# PG13__USB_Ports.net
KiCad netlist of a schematic drawn in Altium Designer
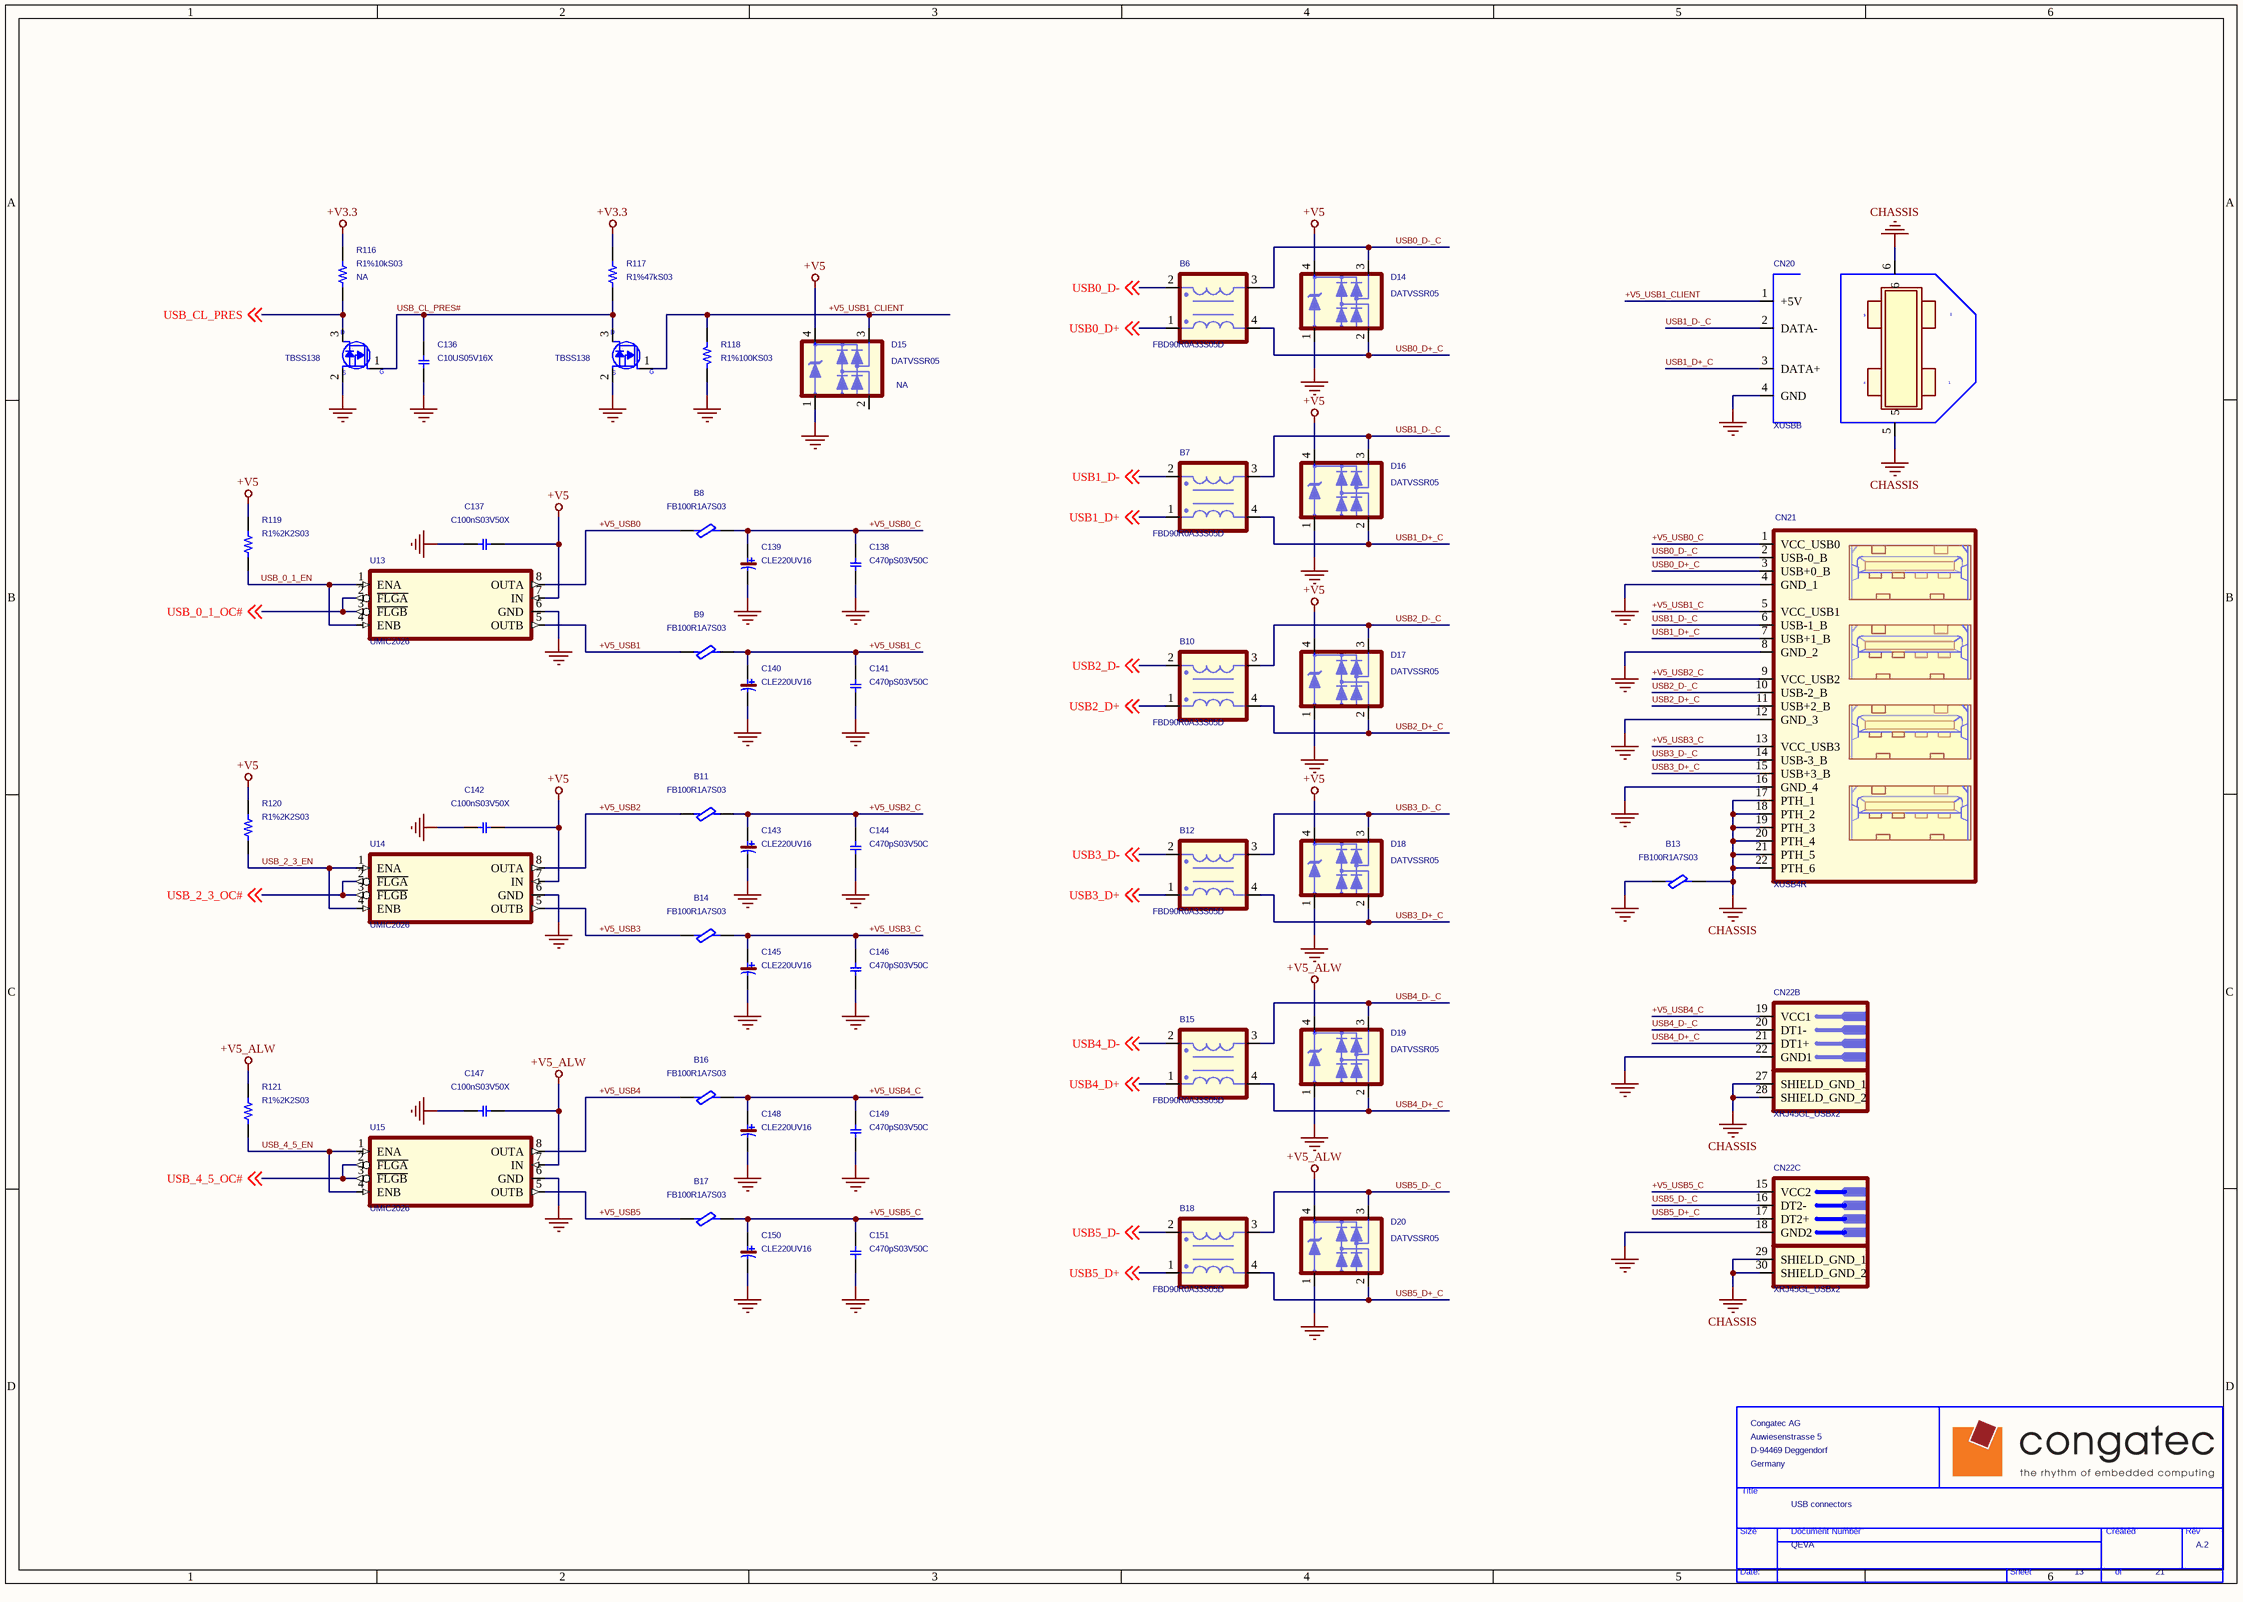
[diagram p0: PG13_ USB Ports.SchDoc]

(export (version "E")
  (design (tool "Eeschema 10.0.6"))
  (components
    (comp (ref "B6")
      (value "FBD90R0A33S05D")
      (description "* Inductor Common-MODE FILTER ACM2012-900-2P SMD")
      (fields (field (name "PART_NUMBER") "43500027") (field (name "PART NUMBER") "1212309007"))
      (libsource (lib "*") (part "1212_FILTER_0"))
    )
    (comp (ref "B7")
      (value "FBD90R0A33S05D")
      (description "* Inductor Common-MODE FILTER ACM2012-900-2P SMD")
      (fields (field (name "PART_NUMBER") "43500027") (field (name "PART NUMBER") "1212309007"))
      (libsource (lib "*") (part "1212_FILTER_0"))
    )
    (comp (ref "B8")
      (value "FB100R1A7S03")
      (description "Bead 120 +-25% 2A SMD 0603 BLM18PG121SN1 WO/Pb")
      (fields (field (name "PART_NUMBER") "43500008") (field (name "PART NUMBER") "1212000056"))
      (libsource (lib "*") (part "1212_BEAD_0"))
    )
    (comp (ref "B9")
      (value "FB100R1A7S03")
      (description "Bead 120 +-25% 2A SMD 0603 BLM18PG121SN1 WO/Pb")
      (fields (field (name "PART_NUMBER") "43500008") (field (name "PART NUMBER") "1212000056"))
      (libsource (lib "*") (part "1212_BEAD_0"))
    )
    (comp (ref "B10")
      (value "FBD90R0A33S05D")
      (description "* Inductor Common-MODE FILTER ACM2012-900-2P SMD")
      (fields (field (name "PART_NUMBER") "43500027") (field (name "PART NUMBER") "1212309007"))
      (libsource (lib "*") (part "1212_FILTER_0"))
    )
    (comp (ref "B11")
      (value "FB100R1A7S03")
      (description "Bead 120 +-25% 2A SMD 0603 BLM18PG121SN1 WO/Pb")
      (fields (field (name "PART_NUMBER") "43500008") (field (name "PART NUMBER") "1212000056"))
      (libsource (lib "*") (part "1212_BEAD_0"))
    )
    (comp (ref "B12")
      (value "FBD90R0A33S05D")
      (description "* Inductor Common-MODE FILTER ACM2012-900-2P SMD")
      (fields (field (name "PART_NUMBER") "43500027") (field (name "PART NUMBER") "1212309007"))
      (libsource (lib "*") (part "1212_FILTER_0"))
    )
    (comp (ref "B13")
      (value "FB100R1A7S03")
      (description "Bead 120 +-25% 2A SMD 0603 BLM18PG121SN1 WO/Pb")
      (fields
        (field (name "PART_NUMBER") "43500008")
        (field (name "MANUFACTURE PART NUMBER") "BLM18PG121SN1")
      )
      (libsource (lib "*") (part "1212_BEAD_0"))
    )
    (comp (ref "B14")
      (value "FB100R1A7S03")
      (description "Bead 120 +-25% 2A SMD 0603 BLM18PG121SN1 WO/Pb")
      (fields (field (name "PART_NUMBER") "43500008") (field (name "PART NUMBER") "1212000056"))
      (libsource (lib "*") (part "1212_BEAD_0"))
    )
    (comp (ref "B15")
      (value "FBD90R0A33S05D")
      (description "* Inductor Common-MODE FILTER ACM2012-900-2P SMD")
      (fields (field (name "PART_NUMBER") "43500027") (field (name "PART NUMBER") "1212309007"))
      (libsource (lib "*") (part "1212_FILTER_0"))
    )
    (comp (ref "B16")
      (value "FB100R1A7S03")
      (description "Bead 120 +-25% 2A SMD 0603 BLM18PG121SN1 WO/Pb")
      (fields (field (name "PART_NUMBER") "43500008") (field (name "PART NUMBER") "1212000056"))
      (libsource (lib "*") (part "1212_BEAD_0"))
    )
    (comp (ref "B17")
      (value "FB100R1A7S03")
      (description "Bead 120 +-25% 2A SMD 0603 BLM18PG121SN1 WO/Pb")
      (fields (field (name "PART_NUMBER") "43500008") (field (name "PART NUMBER") "1212000056"))
      (libsource (lib "*") (part "1212_BEAD_0"))
    )
    (comp (ref "B18")
      (value "FBD90R0A33S05D")
      (description "* Inductor Common-MODE FILTER ACM2012-900-2P SMD")
      (fields (field (name "PART_NUMBER") "43500027") (field (name "PART NUMBER") "1212309007"))
      (libsource (lib "*") (part "1212_FILTER_0"))
    )
    (comp (ref "C136")
      (value "C10US05V16X")
      (description "CAP 10u 6.3V +/-10% SMD 0805 MLCC X5R KEMET")
      (fields (field (name "PART NUMBER") "1100000316") (field (name "TOLERANCE") "10%"))
      (libsource (lib "*") (part "11_C_0"))
    )
    (comp (ref "C137")
      (value "C100nS03V50X")
      (description "CAP 0.1U 50V +-10% SMD 0603 X7R WO/Pb")
      (fields
        (field (name "PART_NUMBER") "41000289")
        (field (name "MANUFACTURE PART NUMBER") "C1608X7R1H104KT223858615649")
      )
      (libsource (lib "*") (part "11_C_0"))
    )
    (comp (ref "C138")
      (value "C470pS03V50C")
      (description "CAP 470pF 50V 10% 0603 SMD  MCC")
      (fields (field (name "PART_NUMBER") "41000322") (field (name "PART NUMBER") "1124547180"))
      (libsource (lib "*") (part "11_C_0"))
    )
    (comp (ref "C139")
      (value "CLE220UV16")
      (description "*CAP 220uF 16V +-20% SMD 6.3?*7.7 EC LOW ESR")
      (fields (field (name "PART_NUMBER") "41000366") (field (name "PART NUMBER") "1111622190"))
      (libsource (lib "*") (part "11_C_POLAR_0"))
    )
    (comp (ref "C140")
      (value "CLE220UV16")
      (description "*CAP 220uF 16V +-20% SMD 6.3?*7.7 EC LOW ESR")
      (fields (field (name "PART_NUMBER") "41000366") (field (name "PART NUMBER") "1111622190"))
      (libsource (lib "*") (part "11_C_POLAR_0"))
    )
    (comp (ref "C141")
      (value "C470pS03V50C")
      (description "CAP 470pF 50V 10% 0603 SMD  MCC")
      (fields (field (name "PART_NUMBER") "41000322") (field (name "PART NUMBER") "1124547180"))
      (libsource (lib "*") (part "11_C_0"))
    )
    (comp (ref "C142")
      (value "C100nS03V50X")
      (description "CAP 0.1U 50V +-10% SMD 0603 X7R WO/Pb")
      (fields (field (name "PART NUMBER") "1100000214") (field (name "TOLERANCE") "10%"))
      (libsource (lib "*") (part "11_C_0"))
    )
    (comp (ref "C143")
      (value "CLE220UV16")
      (description "*CAP 220uF 16V +-20% SMD 6.3?*7.7 EC LOW ESR")
      (fields (field (name "PART_NUMBER") "41000366") (field (name "PART NUMBER") "1111622190"))
      (libsource (lib "*") (part "11_C_POLAR_0"))
    )
    (comp (ref "C144")
      (value "C470pS03V50C")
      (description "CAP 470pF 50V 10% 0603 SMD  MCC")
      (fields (field (name "PART_NUMBER") "41000322") (field (name "PART NUMBER") "1124547180"))
      (libsource (lib "*") (part "11_C_0"))
    )
    (comp (ref "C145")
      (value "CLE220UV16")
      (description "*CAP 220uF 16V +-20% SMD 6.3?*7.7 EC LOW ESR")
      (fields (field (name "PART_NUMBER") "41000366") (field (name "PART NUMBER") "1111622190"))
      (libsource (lib "*") (part "11_C_POLAR_0"))
    )
    (comp (ref "C146")
      (value "C470pS03V50C")
      (description "CAP 470pF 50V 10% 0603 SMD  MCC")
      (fields (field (name "PART_NUMBER") "41000322") (field (name "PART NUMBER") "1124547180"))
      (libsource (lib "*") (part "11_C_0"))
    )
    (comp (ref "C147")
      (value "C100nS03V50X")
      (description "CAP 0.1U 50V +-10% SMD 0603 X7R WO/Pb")
      (fields (field (name "PART NUMBER") "1100000214") (field (name "TOLERANCE") "10%"))
      (libsource (lib "*") (part "11_C_0"))
    )
    (comp (ref "C148")
      (value "CLE220UV16")
      (description "*CAP 220uF 16V +-20% SMD 6.3?*7.7 EC LOW ESR")
      (fields (field (name "PART_NUMBER") "41000366") (field (name "PART NUMBER") "1111622190"))
      (libsource (lib "*") (part "11_C_POLAR_0"))
    )
    (comp (ref "C149")
      (value "C470pS03V50C")
      (description "CAP 470pF 50V 10% 0603 SMD  MCC")
      (fields (field (name "PART_NUMBER") "41000322") (field (name "PART NUMBER") "1124547180"))
      (libsource (lib "*") (part "11_C_0"))
    )
    (comp (ref "C150")
      (value "CLE220UV16")
      (description "*CAP 220uF 16V +-20% SMD 6.3?*7.7 EC LOW ESR")
      (fields (field (name "PART_NUMBER") "41000366") (field (name "PART NUMBER") "1111622190"))
      (libsource (lib "*") (part "11_C_POLAR_0"))
    )
    (comp (ref "C151")
      (value "C470pS03V50C")
      (description "CAP 470pF 50V 10% 0603 SMD  MCC")
      (fields (field (name "PART_NUMBER") "41000322") (field (name "PART NUMBER") "1124547180"))
      (libsource (lib "*") (part "11_C_0"))
    )
    (comp (ref "CN20")
      (value "XUSBB")
      (description "USB CONN. 4P 90D(M) TYPE B SUYIN")
      (fields
        (field (name "PART_NUMBER") "41500326")
        (field (name "MANUFACTURE PART NUMBER") "020123MR004S200PA")
      )
      (libsource (lib "*") (part "1654_USB-BT-V_0"))
    )
    (comp (ref "CN21")
      (value "XUSB4R")
      (description "USB CONN. 16P 90D(M) DIP 4PORT TYPE A")
      (fields
        (field (name "PART NUMBER") "1654000162")
        (field (name "MANUFACTURE PART NUMBER") "0-1734383-1")
      )
      (libsource (lib "*") (part "1654_USBX4-V_ATYPE_0"))
    )
    (comp (ref "CN22")
      (value "XRJ45GL_USBx2")
      (description "PhoneJack RJ45+USB*2 90D(F) W/LED&XFMR DIP")
      (fields (field (name "PART NUMBER") "165250820M") (field (name "PART_NUMBER") "41500328"))
      (libsource (lib "*") (part "1652_RJ45-P3515619W9_0"))
    )
    (comp (ref "D14")
      (value "DATVSSR05")
      (description "Diode TVS SR05.TCT SMD SOT-143 4P 15KV SEMTECH")
      (fields (field (name "PART_NUMBER") "42500011") (field (name "MANUFACTURE PART NUMBER") "SR05.TCT"))
      (libsource (lib "*") (part "130_TVS_SOT-143-SR05_0"))
    )
    (comp (ref "D15")
      (value "DATVSSR05")
      (description "Diode TVS SR05.TCT SMD SOT-143 4P 15KV SEMTECH")
      (fields
        (field (name "MANUFACTURE PART NUMBER") "SR05.TCT")
        (field (name "PART NUMBER") "1300000127")
        (field (name "MOUNTED") "NA")
      )
      (libsource (lib "*") (part "130_TVS_SOT-143-SR05_0"))
    )
    (comp (ref "D16")
      (value "DATVSSR05")
      (description "Diode TVS SR05.TCT SMD SOT-143 4P 15KV SEMTECH")
      (fields (field (name "PART_NUMBER") "42500011") (field (name "MANUFACTURE PART NUMBER") "SR05.TCT"))
      (libsource (lib "*") (part "130_TVS_SOT-143-SR05_0"))
    )
    (comp (ref "D17")
      (value "DATVSSR05")
      (description "Diode TVS SR05.TCT SMD SOT-143 4P 15KV SEMTECH")
      (fields (field (name "PART_NUMBER") "42500011") (field (name "MANUFACTURE PART NUMBER") "SR05.TCT"))
      (libsource (lib "*") (part "130_TVS_SOT-143-SR05_0"))
    )
    (comp (ref "D18")
      (value "DATVSSR05")
      (description "Diode TVS SR05.TCT SMD SOT-143 4P 15KV SEMTECH")
      (fields (field (name "PART_NUMBER") "42500011") (field (name "MANUFACTURE PART NUMBER") "SR05.TCT"))
      (libsource (lib "*") (part "130_TVS_SOT-143-SR05_0"))
    )
    (comp (ref "D19")
      (value "DATVSSR05")
      (description "Diode TVS SR05.TCT SMD SOT-143 4P 15KV SEMTECH")
      (fields (field (name "PART_NUMBER") "42500011") (field (name "PART NUMBER") "1300000127"))
      (libsource (lib "*") (part "130_TVS_SOT-143-SR05_0"))
    )
    (comp (ref "D20")
      (value "DATVSSR05")
      (description "Diode TVS SR05.TCT SMD SOT-143 4P 15KV SEMTECH")
      (fields (field (name "PART_NUMBER") "42500011") (field (name "PART NUMBER") "1300000127"))
      (libsource (lib "*") (part "130_TVS_SOT-143-SR05_0"))
    )
    (comp (ref "Q11")
      (value "TBSS138")
      (description "MOSFET MPN BSS138_NL SMD SOT-23 3P 50V N-channe")
      (fields (field (name "PART_NUMBER") "44000026") (field (name "MANUFACTURE PART NUMBER") "BSS138_NL"))
      (libsource (lib "*") (part "131_SOT-23A_GSD_0"))
    )
    (comp (ref "Q12")
      (value "TBSS138")
      (description "MOSFET MPN BSS138_NL SMD SOT-23 3P 50V N-channe")
      (fields (field (name "PART_NUMBER") "44000026") (field (name "PART NUMBER") "1310000011"))
      (libsource (lib "*") (part "131_SOT-23A_GSD_0"))
    )
    (comp (ref "R116")
      (value "R1%10kS03")
      (description "R 10K 1/10W 1% SMD 0603 CR WO/Pb")
      (fields
        (field (name "MOUNTED") "NA")
        (field (name "MANUFACTURE PART NUMBER") "RCT02***FTP0603WAF1002T5E2322 704 61003LRC0603FR-0710KLRM06FTN1002WR06X8200JT")
        (field (name "TOLERANCE") "1%")
      )
      (libsource (lib "*") (part "10_R_0_Dup1"))
    )
    (comp (ref "R117")
      (value "R1%47kS03")
      (description "47K 1/10W 5% 0603 CR WO/Pb")
      (fields
        (field (name "MANUFACTURE PART NUMBER") "0603WAJ0473T5E232270260473LRM06JTN473")
        (field (name "TOLERANCE") "5%")
      )
      (libsource (lib "*") (part "10_R_0_Dup1"))
    )
    (comp (ref "R118")
      (value "R1%100KS03")
      (description "R 100K 1/10W 1% SMD 0603 CR")
      (fields (field (name "PART_NUMBER") "45501496") (field (name "PART NUMBER") "105A510033"))
      (libsource (lib "*") (part "10_R_0_Dup1"))
    )
    (comp (ref "R119")
      (value "R1%2K2S03")
      (description "R 2.2K 1/10W 1% SMD 0603 CR")
      (fields (field (name "PART_NUMBER") "45502036") (field (name "PART NUMBER") "105A522013"))
      (libsource (lib "*") (part "10_R_0_Dup1"))
    )
    (comp (ref "R120")
      (value "R1%2K2S03")
      (description "R 2.2K 1/10W 1% SMD 0603 CR")
      (fields (field (name "PART_NUMBER") "45502036") (field (name "PART NUMBER") "105A522013"))
      (libsource (lib "*") (part "10_R_0_Dup1"))
    )
    (comp (ref "R121")
      (value "R1%2K2S03")
      (description "R 2.2K 1/10W 1% SMD 0603 CR")
      (fields (field (name "PART_NUMBER") "45502036") (field (name "PART NUMBER") "105A522013"))
      (libsource (lib "*") (part "10_R_0_Dup1"))
    )
    (comp (ref "U13")
      (value "UMIC2026")
      (description "IC SMD MIC2026-1YM SOIC8 WO/Pb MICREL")
      (fields (field (name "PART_NUMBER") "43000105") (field (name "MANUFACTURE PART NUMBER") "MIC2026-1YM"))
      (libsource (lib "*") (part "14S_MICREL_MIC2026-1YM_0"))
    )
    (comp (ref "U14")
      (value "UMIC2026")
      (description "IC SMD MIC2026-1YM SOIC8 WO/Pb MICREL")
      (fields (field (name "PART_NUMBER") "43000105") (field (name "PART NUMBER") "14S2202600"))
      (libsource (lib "*") (part "14S_MICREL_MIC2026-1YM_0"))
    )
    (comp (ref "U15")
      (value "UMIC2026")
      (description "IC SMD MIC2026-1YM SOIC8 WO/Pb MICREL")
      (fields (field (name "PART_NUMBER") "43000105") (field (name "PART NUMBER") "14S2202600"))
      (libsource (lib "*") (part "14S_MICREL_MIC2026-1YM_0"))
    )
  )
  (nets
    (net (code "1") (name "+V3.3") (class "Default")
      (node (ref "R116") (pin "1") (pinfunction "1_1") (pintype "passive"))
      (node (ref "R117") (pin "1") (pinfunction "1_1") (pintype "passive"))
    )
    (net (code "2") (name "+V5") (class "Default")
      (node (ref "C137") (pin "2") (pinfunction "2_2") (pintype "passive"))
      (node (ref "C142") (pin "2") (pinfunction "2_2") (pintype "passive"))
      (node (ref "D14") (pin "4") (pinfunction "CATHODE_4") (pintype "passive"))
      (node (ref "D15") (pin "4") (pinfunction "CATHODE_4") (pintype "passive"))
      (node (ref "D16") (pin "4") (pinfunction "CATHODE_4") (pintype "passive"))
      (node (ref "D17") (pin "4") (pinfunction "CATHODE_4") (pintype "passive"))
      (node (ref "D18") (pin "4") (pinfunction "CATHODE_4") (pintype "passive"))
      (node (ref "R119") (pin "2") (pinfunction "2_2") (pintype "passive"))
      (node (ref "R120") (pin "2") (pinfunction "2_2") (pintype "passive"))
      (node (ref "U13") (pin "7") (pinfunction "IN_7") (pintype "input"))
      (node (ref "U14") (pin "7") (pinfunction "IN_7") (pintype "input"))
    )
    (net (code "3") (name "+V5_ALW") (class "Default")
      (node (ref "C147") (pin "2") (pinfunction "2_2") (pintype "passive"))
      (node (ref "D19") (pin "4") (pinfunction "CATHODE_4") (pintype "passive"))
      (node (ref "D20") (pin "4") (pinfunction "CATHODE_4") (pintype "passive"))
      (node (ref "R121") (pin "2") (pinfunction "2_2") (pintype "passive"))
      (node (ref "U15") (pin "7") (pinfunction "IN_7") (pintype "input"))
    )
    (net (code "4") (name "/+V5_USB0") (class "Default")
      (node (ref "B8") (pin "1") (pinfunction "1_1") (pintype "passive"))
      (node (ref "U13") (pin "8") (pinfunction "OUTA_8") (pintype "output"))
    )
    (net (code "5") (name "/+V5_USB0_C") (class "Default")
      (node (ref "B8") (pin "2") (pinfunction "2_2") (pintype "passive"))
      (node (ref "C138") (pin "1") (pinfunction "1_1") (pintype "passive"))
      (node (ref "C139") (pin "1") (pinfunction "1_1") (pintype "passive"))
      (node (ref "CN21") (pin "1") (pinfunction "VCC_USB0_1") (pintype "passive"))
    )
    (net (code "6") (name "/+V5_USB1") (class "Default")
      (node (ref "B9") (pin "1") (pinfunction "1_1") (pintype "passive"))
      (node (ref "U13") (pin "5") (pinfunction "OUTB_5") (pintype "output"))
    )
    (net (code "7") (name "/+V5_USB1_C") (class "Default")
      (node (ref "B9") (pin "2") (pinfunction "2_2") (pintype "passive"))
      (node (ref "C140") (pin "1") (pinfunction "1_1") (pintype "passive"))
      (node (ref "C141") (pin "1") (pinfunction "1_1") (pintype "passive"))
      (node (ref "CN21") (pin "5") (pinfunction "VCC_USB1_5") (pintype "passive"))
    )
    (net (code "8") (name "/+V5_USB1_CLIENT") (class "Default")
      (node (ref "CN20") (pin "1") (pinfunction "+5V_1") (pintype "passive"))
      (node (ref "D15") (pin "3") (pinfunction "3_3") (pintype "passive"))
      (node (ref "Q12") (pin "1") (pinfunction "G_1") (pintype "passive"))
      (node (ref "R118") (pin "2") (pinfunction "2_2") (pintype "passive"))
    )
    (net (code "9") (name "/+V5_USB2") (class "Default")
      (node (ref "B11") (pin "1") (pinfunction "1_1") (pintype "passive"))
      (node (ref "U14") (pin "8") (pinfunction "OUTA_8") (pintype "output"))
    )
    (net (code "10") (name "/+V5_USB2_C") (class "Default")
      (node (ref "B11") (pin "2") (pinfunction "2_2") (pintype "passive"))
      (node (ref "C143") (pin "1") (pinfunction "1_1") (pintype "passive"))
      (node (ref "C144") (pin "1") (pinfunction "1_1") (pintype "passive"))
      (node (ref "CN21") (pin "9") (pinfunction "VCC_USB2_9") (pintype "passive"))
    )
    (net (code "11") (name "/+V5_USB3") (class "Default")
      (node (ref "B14") (pin "1") (pinfunction "1_1") (pintype "passive"))
      (node (ref "U14") (pin "5") (pinfunction "OUTB_5") (pintype "output"))
    )
    (net (code "12") (name "/+V5_USB3_C") (class "Default")
      (node (ref "B14") (pin "2") (pinfunction "2_2") (pintype "passive"))
      (node (ref "C145") (pin "1") (pinfunction "1_1") (pintype "passive"))
      (node (ref "C146") (pin "1") (pinfunction "1_1") (pintype "passive"))
      (node (ref "CN21") (pin "13") (pinfunction "VCC_USB3_13") (pintype "passive"))
    )
    (net (code "13") (name "/+V5_USB4") (class "Default")
      (node (ref "B16") (pin "1") (pinfunction "1_1") (pintype "passive"))
      (node (ref "U15") (pin "8") (pinfunction "OUTA_8") (pintype "output"))
    )
    (net (code "14") (name "/+V5_USB4_C") (class "Default")
      (node (ref "B16") (pin "2") (pinfunction "2_2") (pintype "passive"))
      (node (ref "C148") (pin "1") (pinfunction "1_1") (pintype "passive"))
      (node (ref "C149") (pin "1") (pinfunction "1_1") (pintype "passive"))
      (node (ref "CN22") (pin "19") (pinfunction "VCC1_19") (pintype "passive"))
    )
    (net (code "15") (name "/+V5_USB5") (class "Default")
      (node (ref "B17") (pin "1") (pinfunction "1_1") (pintype "passive"))
      (node (ref "U15") (pin "5") (pinfunction "OUTB_5") (pintype "output"))
    )
    (net (code "16") (name "/+V5_USB5_C") (class "Default")
      (node (ref "B17") (pin "2") (pinfunction "2_2") (pintype "passive"))
      (node (ref "C150") (pin "1") (pinfunction "1_1") (pintype "passive"))
      (node (ref "C151") (pin "1") (pinfunction "1_1") (pintype "passive"))
      (node (ref "CN22") (pin "15") (pinfunction "VCC2_15") (pintype "passive"))
    )
    (net (code "17") (name "/USB0_D+_C") (class "Default")
      (node (ref "B6") (pin "4") (pinfunction "L4_4") (pintype "passive"))
      (node (ref "CN21") (pin "3") (pinfunction "USB+0_B_3") (pintype "passive"))
      (node (ref "D14") (pin "2") (pinfunction "2_2") (pintype "passive"))
    )
    (net (code "18") (name "/USB0_D-_C") (class "Default")
      (node (ref "B6") (pin "3") (pinfunction "L3_3") (pintype "passive"))
      (node (ref "CN21") (pin "2") (pinfunction "USB-0_B_2") (pintype "passive"))
      (node (ref "D14") (pin "3") (pinfunction "3_3") (pintype "passive"))
    )
    (net (code "19") (name "/USB1_D+_C") (class "Default")
      (node (ref "B7") (pin "4") (pinfunction "L4_4") (pintype "passive"))
      (node (ref "CN20") (pin "3") (pinfunction "DATA+_3") (pintype "passive"))
      (node (ref "CN21") (pin "7") (pinfunction "USB+1_B_7") (pintype "passive"))
      (node (ref "D16") (pin "2") (pinfunction "2_2") (pintype "passive"))
    )
    (net (code "20") (name "/USB1_D-_C") (class "Default")
      (node (ref "B7") (pin "3") (pinfunction "L3_3") (pintype "passive"))
      (node (ref "CN20") (pin "2") (pinfunction "DATA-_2") (pintype "passive"))
      (node (ref "CN21") (pin "6") (pinfunction "USB-1_B_6") (pintype "passive"))
      (node (ref "D16") (pin "3") (pinfunction "3_3") (pintype "passive"))
    )
    (net (code "21") (name "/USB2_D+_C") (class "Default")
      (node (ref "B10") (pin "4") (pinfunction "L4_4") (pintype "passive"))
      (node (ref "CN21") (pin "11") (pinfunction "USB+2_B_11") (pintype "passive"))
      (node (ref "D17") (pin "2") (pinfunction "2_2") (pintype "passive"))
    )
    (net (code "22") (name "/USB2_D-_C") (class "Default")
      (node (ref "B10") (pin "3") (pinfunction "L3_3") (pintype "passive"))
      (node (ref "CN21") (pin "10") (pinfunction "USB-2_B_10") (pintype "passive"))
      (node (ref "D17") (pin "3") (pinfunction "3_3") (pintype "passive"))
    )
    (net (code "23") (name "/USB3_D+_C") (class "Default")
      (node (ref "B12") (pin "4") (pinfunction "L4_4") (pintype "passive"))
      (node (ref "CN21") (pin "15") (pinfunction "USB+3_B_15") (pintype "passive"))
      (node (ref "D18") (pin "2") (pinfunction "2_2") (pintype "passive"))
    )
    (net (code "24") (name "/USB3_D-_C") (class "Default")
      (node (ref "B12") (pin "3") (pinfunction "L3_3") (pintype "passive"))
      (node (ref "CN21") (pin "14") (pinfunction "USB-3_B_14") (pintype "passive"))
      (node (ref "D18") (pin "3") (pinfunction "3_3") (pintype "passive"))
    )
    (net (code "25") (name "/USB4_D+_C") (class "Default")
      (node (ref "B15") (pin "4") (pinfunction "L4_4") (pintype "passive"))
      (node (ref "CN22") (pin "21") (pinfunction "DT1+_21") (pintype "passive"))
      (node (ref "D19") (pin "2") (pinfunction "2_2") (pintype "passive"))
    )
    (net (code "26") (name "/USB4_D-_C") (class "Default")
      (node (ref "B15") (pin "3") (pinfunction "L3_3") (pintype "passive"))
      (node (ref "CN22") (pin "20") (pinfunction "DT1-_20") (pintype "passive"))
      (node (ref "D19") (pin "3") (pinfunction "3_3") (pintype "passive"))
    )
    (net (code "27") (name "/USB5_D+_C") (class "Default")
      (node (ref "B18") (pin "4") (pinfunction "L4_4") (pintype "passive"))
      (node (ref "CN22") (pin "17") (pinfunction "DT2+_17") (pintype "passive"))
      (node (ref "D20") (pin "2") (pinfunction "2_2") (pintype "passive"))
    )
    (net (code "28") (name "/USB5_D-_C") (class "Default")
      (node (ref "B18") (pin "3") (pinfunction "L3_3") (pintype "passive"))
      (node (ref "CN22") (pin "16") (pinfunction "DT2-_16") (pintype "passive"))
      (node (ref "D20") (pin "3") (pinfunction "3_3") (pintype "passive"))
    )
    (net (code "29") (name "/USB_0_1_EN") (class "Default")
      (node (ref "R119") (pin "1") (pinfunction "1_1") (pintype "passive"))
      (node (ref "U13") (pin "1") (pinfunction "ENA_1") (pintype "input"))
      (node (ref "U13") (pin "4") (pinfunction "ENB_4") (pintype "input"))
    )
    (net (code "30") (name "/USB_2_3_EN") (class "Default")
      (node (ref "R120") (pin "1") (pinfunction "1_1") (pintype "passive"))
      (node (ref "U14") (pin "1") (pinfunction "ENA_1") (pintype "input"))
      (node (ref "U14") (pin "4") (pinfunction "ENB_4") (pintype "input"))
    )
    (net (code "31") (name "/USB_4_5_EN") (class "Default")
      (node (ref "R121") (pin "1") (pinfunction "1_1") (pintype "passive"))
      (node (ref "U15") (pin "1") (pinfunction "ENA_1") (pintype "input"))
      (node (ref "U15") (pin "4") (pinfunction "ENB_4") (pintype "input"))
    )
    (net (code "32") (name "/USB_CL_PRES#") (class "Default")
      (node (ref "C136") (pin "1") (pinfunction "1_1") (pintype "passive"))
      (node (ref "Q11") (pin "1") (pinfunction "G_1") (pintype "passive"))
      (node (ref "Q12") (pin "3") (pinfunction "D_3") (pintype "passive"))
      (node (ref "R117") (pin "2") (pinfunction "2_2") (pintype "passive"))
    )
    (net (code "33") (name "CHASSIS") (class "Default")
      (node (ref "B13") (pin "2") (pinfunction "2_2") (pintype "passive"))
      (node (ref "CN20") (pin "5") (pinfunction "5_5") (pintype "passive"))
      (node (ref "CN20") (pin "6") (pinfunction "6_6") (pintype "passive"))
      (node (ref "CN21") (pin "17") (pinfunction "PTH_1_17") (pintype "passive"))
      (node (ref "CN21") (pin "18") (pinfunction "PTH_2_18") (pintype "passive"))
      (node (ref "CN21") (pin "19") (pinfunction "PTH_3_19") (pintype "passive"))
      (node (ref "CN21") (pin "20") (pinfunction "PTH_4_20") (pintype "passive"))
      (node (ref "CN21") (pin "21") (pinfunction "PTH_5_21") (pintype "passive"))
      (node (ref "CN21") (pin "22") (pinfunction "PTH_6_22") (pintype "passive"))
      (node (ref "CN22") (pin "27") (pinfunction "SHIELD_GND_1_27") (pintype "passive"))
      (node (ref "CN22") (pin "28") (pinfunction "SHIELD_GND_2_28") (pintype "passive"))
      (node (ref "CN22") (pin "29") (pinfunction "SHIELD_GND_1_29") (pintype "passive"))
      (node (ref "CN22") (pin "30") (pinfunction "SHIELD_GND_2_30") (pintype "passive"))
    )
    (net (code "34") (name "GND") (class "Default")
      (node (ref "B13") (pin "1") (pinfunction "1_1") (pintype "passive"))
      (node (ref "C136") (pin "2") (pinfunction "2_2") (pintype "passive"))
      (node (ref "C137") (pin "1") (pinfunction "1_1") (pintype "passive"))
      (node (ref "C138") (pin "2") (pinfunction "2_2") (pintype "passive"))
      (node (ref "C139") (pin "2") (pinfunction "2_2") (pintype "passive"))
      (node (ref "C140") (pin "2") (pinfunction "2_2") (pintype "passive"))
      (node (ref "C141") (pin "2") (pinfunction "2_2") (pintype "passive"))
      (node (ref "C142") (pin "1") (pinfunction "1_1") (pintype "passive"))
      (node (ref "C143") (pin "2") (pinfunction "2_2") (pintype "passive"))
      (node (ref "C144") (pin "2") (pinfunction "2_2") (pintype "passive"))
      (node (ref "C145") (pin "2") (pinfunction "2_2") (pintype "passive"))
      (node (ref "C146") (pin "2") (pinfunction "2_2") (pintype "passive"))
      (node (ref "C147") (pin "1") (pinfunction "1_1") (pintype "passive"))
      (node (ref "C148") (pin "2") (pinfunction "2_2") (pintype "passive"))
      (node (ref "C149") (pin "2") (pinfunction "2_2") (pintype "passive"))
      (node (ref "C150") (pin "2") (pinfunction "2_2") (pintype "passive"))
      (node (ref "C151") (pin "2") (pinfunction "2_2") (pintype "passive"))
      (node (ref "CN20") (pin "4") (pinfunction "GND_4") (pintype "passive"))
      (node (ref "CN21") (pin "12") (pinfunction "GND_3_12") (pintype "passive"))
      (node (ref "CN21") (pin "16") (pinfunction "GND_4_16") (pintype "passive"))
      (node (ref "CN21") (pin "4") (pinfunction "GND_1_4") (pintype "passive"))
      (node (ref "CN21") (pin "8") (pinfunction "GND_2_8") (pintype "passive"))
      (node (ref "CN22") (pin "18") (pinfunction "GND2_18") (pintype "passive"))
      (node (ref "CN22") (pin "22") (pinfunction "GND1_22") (pintype "passive"))
      (node (ref "D14") (pin "1") (pinfunction "ANODE_1") (pintype "passive"))
      (node (ref "D15") (pin "1") (pinfunction "ANODE_1") (pintype "passive"))
      (node (ref "D16") (pin "1") (pinfunction "ANODE_1") (pintype "passive"))
      (node (ref "D17") (pin "1") (pinfunction "ANODE_1") (pintype "passive"))
      (node (ref "D18") (pin "1") (pinfunction "ANODE_1") (pintype "passive"))
      (node (ref "D19") (pin "1") (pinfunction "ANODE_1") (pintype "passive"))
      (node (ref "D20") (pin "1") (pinfunction "ANODE_1") (pintype "passive"))
      (node (ref "Q11") (pin "2") (pinfunction "S_2") (pintype "passive"))
      (node (ref "Q12") (pin "2") (pinfunction "S_2") (pintype "passive"))
      (node (ref "R118") (pin "1") (pinfunction "1_1") (pintype "passive"))
      (node (ref "U13") (pin "6") (pinfunction "GND_6") (pintype "power_in"))
      (node (ref "U14") (pin "6") (pinfunction "GND_6") (pintype "power_in"))
      (node (ref "U15") (pin "6") (pinfunction "GND_6") (pintype "power_in"))
    )
    (net (code "35") (name "USB0_D+") (class "Default")
      (node (ref "B6") (pin "1") (pinfunction "L1_1") (pintype "passive"))
    )
    (net (code "36") (name "USB0_D-") (class "Default")
      (node (ref "B6") (pin "2") (pinfunction "L2_2") (pintype "passive"))
    )
    (net (code "37") (name "USB1_D+") (class "Default")
      (node (ref "B7") (pin "1") (pinfunction "L1_1") (pintype "passive"))
    )
    (net (code "38") (name "USB1_D-") (class "Default")
      (node (ref "B7") (pin "2") (pinfunction "L2_2") (pintype "passive"))
    )
    (net (code "39") (name "USB2_D+") (class "Default")
      (node (ref "B10") (pin "1") (pinfunction "L1_1") (pintype "passive"))
    )
    (net (code "40") (name "USB2_D-") (class "Default")
      (node (ref "B10") (pin "2") (pinfunction "L2_2") (pintype "passive"))
    )
    (net (code "41") (name "USB3_D+") (class "Default")
      (node (ref "B12") (pin "1") (pinfunction "L1_1") (pintype "passive"))
    )
    (net (code "42") (name "USB3_D-") (class "Default")
      (node (ref "B12") (pin "2") (pinfunction "L2_2") (pintype "passive"))
    )
    (net (code "43") (name "USB4_D+") (class "Default")
      (node (ref "B15") (pin "1") (pinfunction "L1_1") (pintype "passive"))
    )
    (net (code "44") (name "USB4_D-") (class "Default")
      (node (ref "B15") (pin "2") (pinfunction "L2_2") (pintype "passive"))
    )
    (net (code "45") (name "USB5_D+") (class "Default")
      (node (ref "B18") (pin "1") (pinfunction "L1_1") (pintype "passive"))
    )
    (net (code "46") (name "USB5_D-") (class "Default")
      (node (ref "B18") (pin "2") (pinfunction "L2_2") (pintype "passive"))
    )
    (net (code "47") (name "USB_0_1_OC#") (class "Default")
      (node (ref "U13") (pin "2") (pinfunction "~{FLGA}_2") (pintype "output"))
      (node (ref "U13") (pin "3") (pinfunction "~{FLGB}_3") (pintype "output"))
    )
    (net (code "48") (name "USB_2_3_OC#") (class "Default")
      (node (ref "U14") (pin "2") (pinfunction "~{FLGA}_2") (pintype "output"))
      (node (ref "U14") (pin "3") (pinfunction "~{FLGB}_3") (pintype "output"))
    )
    (net (code "49") (name "USB_4_5_OC#") (class "Default")
      (node (ref "U15") (pin "2") (pinfunction "~{FLGA}_2") (pintype "output"))
      (node (ref "U15") (pin "3") (pinfunction "~{FLGB}_3") (pintype "output"))
    )
    (net (code "50") (name "USB_CL_PRES") (class "Default")
      (node (ref "Q11") (pin "3") (pinfunction "D_3") (pintype "passive"))
      (node (ref "R116") (pin "2") (pinfunction "2_2") (pintype "passive"))
    )
    (net (code "51") (name "unconnected-(D15-Pad2)") (class "Default")
      (node (ref "D15") (pin "2") (pinfunction "2_2") (pintype "passive"))
    )
  )
)
